# BlueBox-Amp_Speaker_Protection.net
KiCad netlist of a schematic drawn in Altium Designer
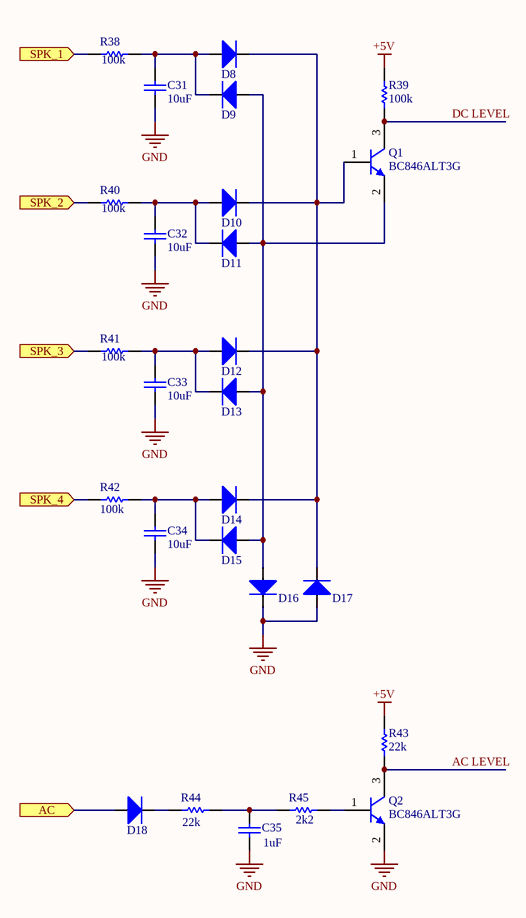
[diagram p0: BlueBox-Amp [Speaker Protection].SchDoc]

(export (version "E")
  (design (tool "Eeschema 10.0.6"))
  (components
    (comp (ref "C31")
      (value "10uF")
      (footprint "CAPC1206(3216)190_M")
      (description "CAP 10uF 50V ±10% 1206 (3216 Metric) Thickness 1.9mm SMD")
      (fields (field (name "TOLERANCE") "±10%") (field (name "Comment") "CAP 10uF 50V 1206(3216)"))
      (libsource (lib "Altium Content Vault") (part "CMP-1037-04982-1"))
    )
    (comp (ref "C32")
      (value "10uF")
      (footprint "CAPC1206(3216)190_M")
      (description "CAP 10uF 50V ±10% 1206 (3216 Metric) Thickness 1.9mm SMD")
      (fields (field (name "TOLERANCE") "±10%") (field (name "Comment") "CAP 10uF 50V 1206(3216)"))
      (libsource (lib "Altium Content Vault") (part "CMP-1037-04982-1"))
    )
    (comp (ref "C33")
      (value "10uF")
      (footprint "CAPC1206(3216)190_M")
      (description "CAP 10uF 50V ±10% 1206 (3216 Metric) Thickness 1.9mm SMD")
      (fields (field (name "TOLERANCE") "±10%") (field (name "Comment") "CAP 10uF 50V 1206(3216)"))
      (libsource (lib "Altium Content Vault") (part "CMP-1037-04982-1"))
    )
    (comp (ref "C34")
      (value "10uF")
      (footprint "CAPC1206(3216)190_M")
      (description "CAP 10uF 50V ±10% 1206 (3216 Metric) Thickness 1.9mm SMD")
      (fields (field (name "TOLERANCE") "±10%") (field (name "Comment") "CAP 10uF 50V 1206(3216)"))
      (libsource (lib "Altium Content Vault") (part "CMP-1037-04982-1"))
    )
    (comp (ref "C35")
      (value "1uF")
      (footprint "CAPC0603(1608)100_L")
      (description "CAP 1uF 50V ±10% 0603 (1608 Metric) Thickness 1mm SMD")
      (fields (field (name "TOLERANCE") "±10%") (field (name "Comment") "CAP 1uF 50V 0603(1608)"))
      (libsource (lib "Altium Content Vault") (part "CMP-1035-02745-1"))
    )
    (comp (ref "D8")
      (value "1N4148WS")
      (footprint "SOD323")
      (description "Diode")
      (libsource (lib "DEV - Diode") (part "1N4148WS"))
    )
    (comp (ref "D9")
      (value "1N4148WS")
      (footprint "SOD323")
      (description "Diode")
      (libsource (lib "DEV - Diode") (part "1N4148WS"))
    )
    (comp (ref "D10")
      (value "1N4148WS")
      (footprint "SOD323")
      (description "Diode")
      (libsource (lib "DEV - Diode") (part "1N4148WS"))
    )
    (comp (ref "D11")
      (value "1N4148WS")
      (footprint "SOD323")
      (description "Diode")
      (libsource (lib "DEV - Diode") (part "1N4148WS"))
    )
    (comp (ref "D12")
      (value "1N4148WS")
      (footprint "SOD323")
      (description "Diode")
      (libsource (lib "DEV - Diode") (part "1N4148WS"))
    )
    (comp (ref "D13")
      (value "1N4148WS")
      (footprint "SOD323")
      (description "Diode")
      (libsource (lib "DEV - Diode") (part "1N4148WS"))
    )
    (comp (ref "D14")
      (value "1N4148WS")
      (footprint "SOD323")
      (description "Diode")
      (libsource (lib "DEV - Diode") (part "1N4148WS"))
    )
    (comp (ref "D15")
      (value "1N4148WS")
      (footprint "SOD323")
      (description "Diode")
      (libsource (lib "DEV - Diode") (part "1N4148WS"))
    )
    (comp (ref "D16")
      (value "1N4148WS")
      (footprint "SOD323")
      (description "Diode")
      (libsource (lib "DEV - Diode") (part "1N4148WS"))
    )
    (comp (ref "D17")
      (value "1N4148WS")
      (footprint "SOD323")
      (description "Diode")
      (libsource (lib "DEV - Diode") (part "1N4148WS"))
    )
    (comp (ref "D18")
      (value "1N4148WS")
      (footprint "SOD323")
      (description "Diode")
      (libsource (lib "DEV - Diode") (part "1N4148WS"))
    )
    (comp (ref "Q1")
      (value "BC846ALT3G")
      (footprint "ONSC-SOT-23-3-318-08_V")
      (description "General Purpose Transistor, NPN Silicon, 3-Pin SOT-23, Pb-Free, Tape and Reel")
      (fields (field (name "MANUFACTURER") "On Semiconductor"))
      (libsource (lib "Altium Content Vault") (part "ONSC-NPN-B1E2C3-3"))
    )
    (comp (ref "Q2")
      (value "BC846ALT3G")
      (footprint "ONSC-SOT-23-3-318-08_V")
      (description "General Purpose Transistor, NPN Silicon, 3-Pin SOT-23, Pb-Free, Tape and Reel")
      (fields (field (name "MANUFACTURER") "On Semiconductor"))
      (libsource (lib "Altium Content Vault") (part "ONSC-NPN-B1E2C3-3"))
    )
    (comp (ref "R38")
      (value "100k")
      (footprint "RESC0603(1608)_N")
      (description "100K 0.1W 1% 0603 (1608 Metric)  SMD")
      (fields (field (name "POWER") "0.1 W") (field (name "TOLERANCE") "1 %"))
      (libsource (lib "Altium Content Vault") (part "CMP-1012-00736-1"))
    )
    (comp (ref "R39")
      (value "100k")
      (footprint "RESC0603(1608)_N")
      (description "100K 0.1W 1% 0603 (1608 Metric)  SMD")
      (fields (field (name "POWER") "0.1 W") (field (name "TOLERANCE") "1 %"))
      (libsource (lib "Altium Content Vault") (part "CMP-1012-00736-1"))
    )
    (comp (ref "R40")
      (value "100k")
      (footprint "RESC0603(1608)_N")
      (description "100K 0.1W 1% 0603 (1608 Metric)  SMD")
      (fields (field (name "POWER") "0.1 W") (field (name "TOLERANCE") "1 %"))
      (libsource (lib "Altium Content Vault") (part "CMP-1012-00736-1"))
    )
    (comp (ref "R41")
      (value "100k")
      (footprint "RESC0603(1608)_N")
      (description "100K 0.1W 1% 0603 (1608 Metric)  SMD")
      (fields (field (name "POWER") "0.1 W") (field (name "TOLERANCE") "1 %"))
      (libsource (lib "Altium Content Vault") (part "CMP-1012-00736-1"))
    )
    (comp (ref "R42")
      (value "100k")
      (footprint "RESC0603(1608)_N")
      (description "100K 0.1W 1% 0603 (1608 Metric)  SMD")
      (fields (field (name "POWER") "0.1 W") (field (name "TOLERANCE") "1 %"))
      (libsource (lib "Altium Content Vault") (part "CMP-1012-00736-1"))
    )
    (comp (ref "R43")
      (value "22k")
      (footprint "RESC0603(1608)_L")
      (description "22K 0.1W 1% 0603 (1608 Metric)  SMD")
      (fields (field (name "POWER") "0.1 W") (field (name "TOLERANCE") "1 %"))
      (libsource (lib "Altium Content Vault") (part "CMP-1012-00659-1"))
    )
    (comp (ref "R44")
      (value "22k")
      (footprint "RESC0603(1608)_L")
      (description "22K 0.1W 1% 0603 (1608 Metric)  SMD")
      (fields (field (name "POWER") "0.1 W") (field (name "TOLERANCE") "1 %"))
      (libsource (lib "Altium Content Vault") (part "CMP-1012-00659-1"))
    )
    (comp (ref "R45")
      (value "2k2")
      (footprint "RESC0603(1608)_L")
      (description "2K2 0.1W 1% 0603 (1608 Metric)  SMD")
      (fields (field (name "TOLERANCE") "1 %") (field (name "POWER") "0.1 W"))
      (libsource (lib "Altium Content Vault") (part "CMP-1012-00546-1"))
    )
  )
  (nets
    (net (code "1") (name "+5V") (class "Default")
      (node (ref "R39") (pin "2") (pinfunction "2_2") (pintype "passive"))
      (node (ref "R43") (pin "2") (pinfunction "2_2") (pintype "passive"))
    )
    (net (code "2") (name "/AC") (class "Default")
      (node (ref "D18") (pin "1") (pinfunction "A_1") (pintype "passive"))
    )
    (net (code "3") (name "/AC LEVEL") (class "Default")
      (node (ref "Q2") (pin "3") (pinfunction "C_3") (pintype "passive"))
      (node (ref "R43") (pin "1") (pinfunction "1_1") (pintype "passive"))
    )
    (net (code "4") (name "/DC LEVEL") (class "Default")
      (node (ref "Q1") (pin "3") (pinfunction "C_3") (pintype "passive"))
      (node (ref "R39") (pin "1") (pinfunction "1_1") (pintype "passive"))
    )
    (net (code "5") (name "/SPK_1") (class "Default")
      (node (ref "R38") (pin "1") (pinfunction "1_1") (pintype "passive"))
    )
    (net (code "6") (name "/SPK_2") (class "Default")
      (node (ref "R40") (pin "1") (pinfunction "1_1") (pintype "passive"))
    )
    (net (code "7") (name "/SPK_3") (class "Default")
      (node (ref "R41") (pin "1") (pinfunction "1_1") (pintype "passive"))
    )
    (net (code "8") (name "/SPK_4") (class "Default")
      (node (ref "R42") (pin "1") (pinfunction "1_1") (pintype "passive"))
    )
    (net (code "9") (name "GND") (class "Default")
      (node (ref "C31") (pin "1") (pinfunction "1_1") (pintype "passive"))
      (node (ref "C32") (pin "1") (pinfunction "1_1") (pintype "passive"))
      (node (ref "C33") (pin "1") (pinfunction "1_1") (pintype "passive"))
      (node (ref "C34") (pin "1") (pinfunction "1_1") (pintype "passive"))
      (node (ref "C35") (pin "1") (pinfunction "1_1") (pintype "passive"))
      (node (ref "D16") (pin "2") (pinfunction "K_2") (pintype "passive"))
      (node (ref "D17") (pin "1") (pinfunction "A_1") (pintype "passive"))
      (node (ref "Q2") (pin "2") (pinfunction "E_2") (pintype "passive"))
    )
    (net (code "10") (name "Net-(C35-Pad2)") (class "Default")
      (node (ref "C35") (pin "2") (pinfunction "2_2") (pintype "passive"))
      (node (ref "R44") (pin "2") (pinfunction "2_2") (pintype "passive"))
      (node (ref "R45") (pin "1") (pinfunction "1_1") (pintype "passive"))
    )
    (net (code "11") (name "Net-(D8-A)") (class "Default")
      (node (ref "C31") (pin "2") (pinfunction "2_2") (pintype "passive"))
      (node (ref "D8") (pin "1") (pinfunction "A_1") (pintype "passive"))
      (node (ref "D9") (pin "2") (pinfunction "K_2") (pintype "passive"))
      (node (ref "R38") (pin "2") (pinfunction "2_2") (pintype "passive"))
    )
    (net (code "12") (name "Net-(D10-A)") (class "Default")
      (node (ref "C32") (pin "2") (pinfunction "2_2") (pintype "passive"))
      (node (ref "D10") (pin "1") (pinfunction "A_1") (pintype "passive"))
      (node (ref "D11") (pin "2") (pinfunction "K_2") (pintype "passive"))
      (node (ref "R40") (pin "2") (pinfunction "2_2") (pintype "passive"))
    )
    (net (code "13") (name "Net-(D10-K)") (class "Default")
      (node (ref "D10") (pin "2") (pinfunction "K_2") (pintype "passive"))
      (node (ref "D12") (pin "2") (pinfunction "K_2") (pintype "passive"))
      (node (ref "D14") (pin "2") (pinfunction "K_2") (pintype "passive"))
      (node (ref "D17") (pin "2") (pinfunction "K_2") (pintype "passive"))
      (node (ref "D8") (pin "2") (pinfunction "K_2") (pintype "passive"))
      (node (ref "Q1") (pin "1") (pinfunction "B_1") (pintype "passive"))
    )
    (net (code "14") (name "Net-(D11-A)") (class "Default")
      (node (ref "D11") (pin "1") (pinfunction "A_1") (pintype "passive"))
      (node (ref "D13") (pin "1") (pinfunction "A_1") (pintype "passive"))
      (node (ref "D15") (pin "1") (pinfunction "A_1") (pintype "passive"))
      (node (ref "D16") (pin "1") (pinfunction "A_1") (pintype "passive"))
      (node (ref "D9") (pin "1") (pinfunction "A_1") (pintype "passive"))
      (node (ref "Q1") (pin "2") (pinfunction "E_2") (pintype "passive"))
    )
    (net (code "15") (name "Net-(D12-A)") (class "Default")
      (node (ref "C33") (pin "2") (pinfunction "2_2") (pintype "passive"))
      (node (ref "D12") (pin "1") (pinfunction "A_1") (pintype "passive"))
      (node (ref "D13") (pin "2") (pinfunction "K_2") (pintype "passive"))
      (node (ref "R41") (pin "2") (pinfunction "2_2") (pintype "passive"))
    )
    (net (code "16") (name "Net-(D14-A)") (class "Default")
      (node (ref "C34") (pin "2") (pinfunction "2_2") (pintype "passive"))
      (node (ref "D14") (pin "1") (pinfunction "A_1") (pintype "passive"))
      (node (ref "D15") (pin "2") (pinfunction "K_2") (pintype "passive"))
      (node (ref "R42") (pin "2") (pinfunction "2_2") (pintype "passive"))
    )
    (net (code "17") (name "Net-(D18-K)") (class "Default")
      (node (ref "D18") (pin "2") (pinfunction "K_2") (pintype "passive"))
      (node (ref "R44") (pin "1") (pinfunction "1_1") (pintype "passive"))
    )
    (net (code "18") (name "Net-(Q2-B)") (class "Default")
      (node (ref "Q2") (pin "1") (pinfunction "B_1") (pintype "passive"))
      (node (ref "R45") (pin "2") (pinfunction "2_2") (pintype "passive"))
    )
  )
)
